# Sheet1.net
KiCad netlist of a schematic drawn in Altium Designer
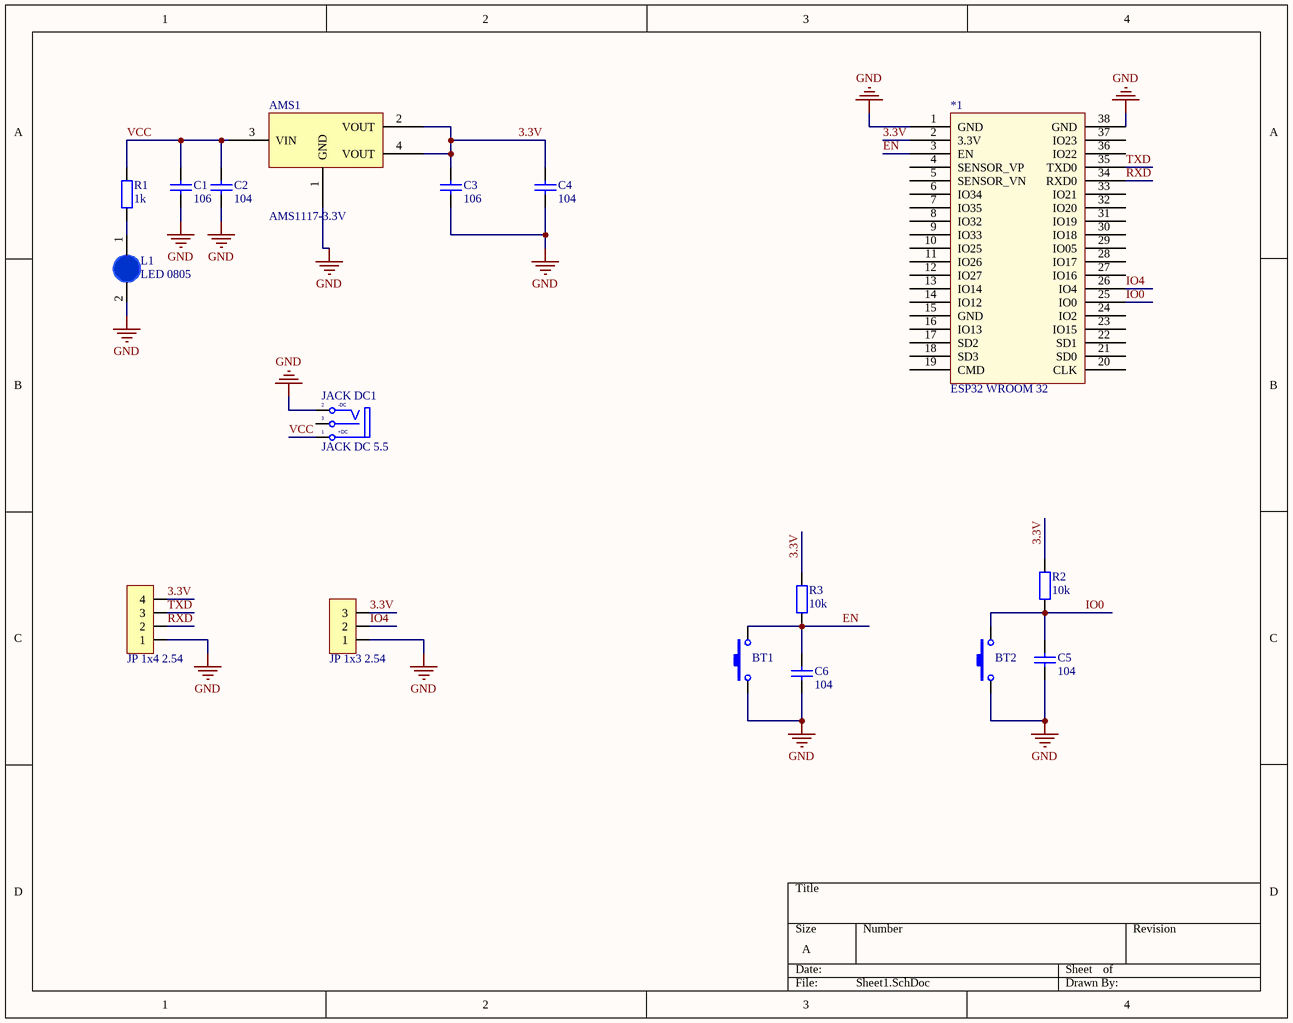
[diagram p0: Sheet1.SchDoc]

(export (version "E")
  (design (tool "Eeschema 10.0.6"))
  (components
    (comp (ref "*1")
      (value "ESP32 WROOM 32")
      (footprint "ESP32-WROOM-32D")
      (libsource (lib "Altium_Lib_by_KhueNguyenCreator") (part "ESP32 WROOM 32"))
    )
    (comp (ref "AMS1")
      (value "AMS1117-3.3V")
      (footprint "SOT223")
      (description "Dán")
      (libsource (lib "Altium_Lib_by_KhueNguyenCreator") (part "AMS1117 SMD"))
    )
    (comp (ref "BT1")
      (value "Nut Nhan 2 Chan SMD 3x6x2.5")
      (footprint "Nut Nhan 2 Chan SMD 3x6x2.5")
      (libsource (lib "Altium_Lib_by_KhueNguyenCreator") (part "Nut Nhan 2 Chan SMD 3x6x2.5"))
    )
    (comp (ref "BT2")
      (value "Nut Nhan 2 Chan SMD 3x6x2.5")
      (footprint "Nut Nhan 2 Chan SMD 3x6x2.5")
      (libsource (lib "Altium_Lib_by_KhueNguyenCreator") (part "Nut Nhan 2 Chan SMD 3x6x2.5"))
    )
    (comp (ref "C1")
      (value "106")
      (footprint "tu 0805")
      (description "Dán")
      (libsource (lib "Altium_Lib_by_KhueNguyenCreator") (part "Tu 0805 106 16V 10%"))
    )
    (comp (ref "C2")
      (value "104")
      (footprint "tu 0805")
      (description "Dán")
      (libsource (lib "Altium_Lib_by_KhueNguyenCreator") (part "Tu 0805 104 50V 10%"))
    )
    (comp (ref "C3")
      (value "106")
      (footprint "tu 0805")
      (description "Dán")
      (libsource (lib "Altium_Lib_by_KhueNguyenCreator") (part "Tu 0805 106 16V 10%"))
    )
    (comp (ref "C4")
      (value "104")
      (footprint "tu 0805")
      (description "Dán")
      (libsource (lib "Altium_Lib_by_KhueNguyenCreator") (part "Tu 0805 104 50V 10%"))
    )
    (comp (ref "C5")
      (value "104")
      (footprint "tu 0805")
      (description "Dán")
      (libsource (lib "Altium_Lib_by_KhueNguyenCreator") (part "Tu 0805 104 50V 10%"))
    )
    (comp (ref "C6")
      (value "104")
      (footprint "tu 0805")
      (description "Dán")
      (libsource (lib "Altium_Lib_by_KhueNguyenCreator") (part "Tu 0805 104 50V 10%"))
    )
    (comp (ref "JACK DC1")
      (value "JACK DC 5.5")
      (footprint "JACK DC 5.5")
      (libsource (lib "Altium_Lib_by_KhueNguyenCreator") (part "JACK DC 5.5"))
    )
    (comp (ref "JP1")
      (value "JP 1x4 2.54")
      (footprint "JP 1x4 DC")
      (description "Cắm")
      (libsource (lib "Altium_Lib_by_KhueNguyenCreator") (part "JP 1x4 2.54 Duc Cong"))
    )
    (comp (ref "JP2")
      (value "JP 1x3 2.54")
      (footprint "JP 1x3 DC")
      (description "Cắm")
      (libsource (lib "Altium_Lib_by_KhueNguyenCreator") (part "JP 1x3 2.54 Duc Cong"))
    )
    (comp (ref "L1")
      (value "LED 0805")
      (footprint "LED-0805-Blue")
      (description "Dán")
      (libsource (lib "Altium_Lib_by_KhueNguyenCreator") (part "LED 0805 Xanh Duong"))
    )
    (comp (ref "R1")
      (value "1k")
      (footprint "tro smd 0603")
      (description "Dán")
      (libsource (lib "Altium_Lib_by_KhueNguyenCreator") (part "Tro 0603 1% 1k"))
    )
    (comp (ref "R2")
      (value "10k")
      (footprint "tro smd 0603")
      (description "Dán")
      (libsource (lib "Altium_Lib_by_KhueNguyenCreator") (part "Tro 0603 1% 10k"))
    )
    (comp (ref "R3")
      (value "10k")
      (footprint "tro smd 0603")
      (description "Dán")
      (libsource (lib "Altium_Lib_by_KhueNguyenCreator") (part "Tro 0603 1% 10k"))
    )
  )
  (nets
    (net (code "1") (name "/3.3V") (class "Default")
      (node (ref "*1") (pin "2") (pinfunction "3.3V_2") (pintype "passive"))
      (node (ref "AMS1") (pin "2") (pinfunction "VOUT_2") (pintype "passive"))
      (node (ref "AMS1") (pin "4") (pinfunction "VOUT_4") (pintype "passive"))
      (node (ref "C3") (pin "1") (pinfunction "1_1") (pintype "passive"))
      (node (ref "C4") (pin "1") (pinfunction "1_1") (pintype "passive"))
      (node (ref "JP1") (pin "4") (pinfunction "4_4") (pintype "passive"))
      (node (ref "JP2") (pin "3") (pinfunction "3_3") (pintype "passive"))
      (node (ref "R2") (pin "2") (pinfunction "2_2") (pintype "passive"))
      (node (ref "R3") (pin "2") (pinfunction "2_2") (pintype "passive"))
    )
    (net (code "2") (name "/EN") (class "Default")
      (node (ref "*1") (pin "3") (pinfunction "EN_3") (pintype "passive"))
      (node (ref "BT1") (pin "2") (pinfunction "2_2") (pintype "passive"))
      (node (ref "C6") (pin "1") (pinfunction "1_1") (pintype "passive"))
      (node (ref "R3") (pin "1") (pinfunction "1_1") (pintype "passive"))
    )
    (net (code "3") (name "/IO0") (class "Default")
      (node (ref "*1") (pin "25") (pinfunction "IO0_25") (pintype "passive"))
      (node (ref "BT2") (pin "2") (pinfunction "2_2") (pintype "passive"))
      (node (ref "C5") (pin "1") (pinfunction "1_1") (pintype "passive"))
      (node (ref "R2") (pin "1") (pinfunction "1_1") (pintype "passive"))
    )
    (net (code "4") (name "/IO4") (class "Default")
      (node (ref "*1") (pin "26") (pinfunction "IO4_26") (pintype "passive"))
      (node (ref "JP2") (pin "2") (pinfunction "2_2") (pintype "passive"))
    )
    (net (code "5") (name "/RXD") (class "Default")
      (node (ref "*1") (pin "34") (pinfunction "RXD0_34") (pintype "passive"))
      (node (ref "JP1") (pin "2") (pinfunction "2_2") (pintype "passive"))
    )
    (net (code "6") (name "/TXD") (class "Default")
      (node (ref "*1") (pin "35") (pinfunction "TXD0_35") (pintype "passive"))
      (node (ref "JP1") (pin "3") (pinfunction "3_3") (pintype "passive"))
    )
    (net (code "7") (name "/VCC") (class "Default")
      (node (ref "AMS1") (pin "3") (pinfunction "VIN_3") (pintype "passive"))
      (node (ref "C1") (pin "1") (pinfunction "1_1") (pintype "passive"))
      (node (ref "C2") (pin "1") (pinfunction "1_1") (pintype "passive"))
      (node (ref "JACK DC1") (pin "1") (pinfunction "T_1") (pintype "passive"))
      (node (ref "R1") (pin "2") (pinfunction "2_2") (pintype "passive"))
    )
    (net (code "8") (name "GND") (class "Default")
      (node (ref "*1") (pin "1") (pinfunction "GND_1") (pintype "passive"))
      (node (ref "*1") (pin "38") (pinfunction "GND_38") (pintype "passive"))
      (node (ref "AMS1") (pin "1") (pinfunction "GND_1") (pintype "passive"))
      (node (ref "BT1") (pin "1") (pinfunction "1_1") (pintype "passive"))
      (node (ref "BT2") (pin "1") (pinfunction "1_1") (pintype "passive"))
      (node (ref "C1") (pin "2") (pinfunction "2_2") (pintype "passive"))
      (node (ref "C2") (pin "2") (pinfunction "2_2") (pintype "passive"))
      (node (ref "C3") (pin "2") (pinfunction "2_2") (pintype "passive"))
      (node (ref "C4") (pin "2") (pinfunction "2_2") (pintype "passive"))
      (node (ref "C5") (pin "2") (pinfunction "2_2") (pintype "passive"))
      (node (ref "C6") (pin "2") (pinfunction "2_2") (pintype "passive"))
      (node (ref "JACK DC1") (pin "2") (pinfunction "TN_2") (pintype "passive"))
      (node (ref "JP1") (pin "1") (pinfunction "1_1") (pintype "passive"))
      (node (ref "JP2") (pin "1") (pinfunction "1_1") (pintype "passive"))
      (node (ref "L1") (pin "2") (pinfunction "K_2") (pintype "passive"))
    )
    (net (code "9") (name "Net-(L1-A)") (class "Default")
      (node (ref "L1") (pin "1") (pinfunction "A_1") (pintype "passive"))
      (node (ref "R1") (pin "1") (pinfunction "1_1") (pintype "passive"))
    )
    (net (code "10") (name "unconnected-(*1-CLK-Pad20)") (class "Default")
      (node (ref "*1") (pin "20") (pinfunction "CLK_20") (pintype "passive"))
    )
    (net (code "11") (name "unconnected-(*1-CMD-Pad19)") (class "Default")
      (node (ref "*1") (pin "19") (pinfunction "CMD_19") (pintype "passive"))
    )
    (net (code "12") (name "unconnected-(*1-GND-Pad15)") (class "Default")
      (node (ref "*1") (pin "15") (pinfunction "GND_15") (pintype "passive"))
    )
    (net (code "13") (name "unconnected-(*1-IO2-Pad24)") (class "Default")
      (node (ref "*1") (pin "24") (pinfunction "IO2_24") (pintype "passive"))
    )
    (net (code "14") (name "unconnected-(*1-IO05-Pad29)") (class "Default")
      (node (ref "*1") (pin "29") (pinfunction "IO05_29") (pintype "passive"))
    )
    (net (code "15") (name "unconnected-(*1-IO12-Pad14)") (class "Default")
      (node (ref "*1") (pin "14") (pinfunction "IO12_14") (pintype "passive"))
    )
    (net (code "16") (name "unconnected-(*1-IO13-Pad16)") (class "Default")
      (node (ref "*1") (pin "16") (pinfunction "IO13_16") (pintype "passive"))
    )
    (net (code "17") (name "unconnected-(*1-IO14-Pad13)") (class "Default")
      (node (ref "*1") (pin "13") (pinfunction "IO14_13") (pintype "passive"))
    )
    (net (code "18") (name "unconnected-(*1-IO15-Pad23)") (class "Default")
      (node (ref "*1") (pin "23") (pinfunction "IO15_23") (pintype "passive"))
    )
    (net (code "19") (name "unconnected-(*1-IO16-Pad27)") (class "Default")
      (node (ref "*1") (pin "27") (pinfunction "IO16_27") (pintype "passive"))
    )
    (net (code "20") (name "unconnected-(*1-IO17-Pad28)") (class "Default")
      (node (ref "*1") (pin "28") (pinfunction "IO17_28") (pintype "passive"))
    )
    (net (code "21") (name "unconnected-(*1-IO18-Pad30)") (class "Default")
      (node (ref "*1") (pin "30") (pinfunction "IO18_30") (pintype "passive"))
    )
    (net (code "22") (name "unconnected-(*1-IO19-Pad31)") (class "Default")
      (node (ref "*1") (pin "31") (pinfunction "IO19_31") (pintype "passive"))
    )
    (net (code "23") (name "unconnected-(*1-IO20-Pad32)") (class "Default")
      (node (ref "*1") (pin "32") (pinfunction "IO20_32") (pintype "passive"))
    )
    (net (code "24") (name "unconnected-(*1-IO21-Pad33)") (class "Default")
      (node (ref "*1") (pin "33") (pinfunction "IO21_33") (pintype "passive"))
    )
    (net (code "25") (name "unconnected-(*1-IO22-Pad36)") (class "Default")
      (node (ref "*1") (pin "36") (pinfunction "IO22_36") (pintype "passive"))
    )
    (net (code "26") (name "unconnected-(*1-IO23-Pad37)") (class "Default")
      (node (ref "*1") (pin "37") (pinfunction "IO23_37") (pintype "passive"))
    )
    (net (code "27") (name "unconnected-(*1-IO25-Pad10)") (class "Default")
      (node (ref "*1") (pin "10") (pinfunction "IO25_10") (pintype "passive"))
    )
    (net (code "28") (name "unconnected-(*1-IO26-Pad11)") (class "Default")
      (node (ref "*1") (pin "11") (pinfunction "IO26_11") (pintype "passive"))
    )
    (net (code "29") (name "unconnected-(*1-IO27-Pad12)") (class "Default")
      (node (ref "*1") (pin "12") (pinfunction "IO27_12") (pintype "passive"))
    )
    (net (code "30") (name "unconnected-(*1-IO32-Pad8)") (class "Default")
      (node (ref "*1") (pin "8") (pinfunction "IO32_8") (pintype "passive"))
    )
    (net (code "31") (name "unconnected-(*1-IO33-Pad9)") (class "Default")
      (node (ref "*1") (pin "9") (pinfunction "IO33_9") (pintype "passive"))
    )
    (net (code "32") (name "unconnected-(*1-IO34-Pad6)") (class "Default")
      (node (ref "*1") (pin "6") (pinfunction "IO34_6") (pintype "passive"))
    )
    (net (code "33") (name "unconnected-(*1-IO35-Pad7)") (class "Default")
      (node (ref "*1") (pin "7") (pinfunction "IO35_7") (pintype "passive"))
    )
    (net (code "34") (name "unconnected-(*1-SD0-Pad21)") (class "Default")
      (node (ref "*1") (pin "21") (pinfunction "SD0_21") (pintype "passive"))
    )
    (net (code "35") (name "unconnected-(*1-SD1-Pad22)") (class "Default")
      (node (ref "*1") (pin "22") (pinfunction "SD1_22") (pintype "passive"))
    )
    (net (code "36") (name "unconnected-(*1-SD2-Pad17)") (class "Default")
      (node (ref "*1") (pin "17") (pinfunction "SD2_17") (pintype "passive"))
    )
    (net (code "37") (name "unconnected-(*1-SD3-Pad18)") (class "Default")
      (node (ref "*1") (pin "18") (pinfunction "SD3_18") (pintype "passive"))
    )
    (net (code "38") (name "unconnected-(*1-SENSOR_VN-Pad5)") (class "Default")
      (node (ref "*1") (pin "5") (pinfunction "SENSOR_VN_5") (pintype "passive"))
    )
    (net (code "39") (name "unconnected-(*1-SENSOR_VP-Pad4)") (class "Default")
      (node (ref "*1") (pin "4") (pinfunction "SENSOR_VP_4") (pintype "passive"))
    )
    (net (code "40") (name "unconnected-(JACK DC1-S-Pad3)") (class "Default")
      (node (ref "JACK DC1") (pin "3") (pinfunction "S_3") (pintype "power_in"))
    )
  )
)
